# circuitPendulum8TIA.net
KiCad netlist of a schematic drawn in EAGLE
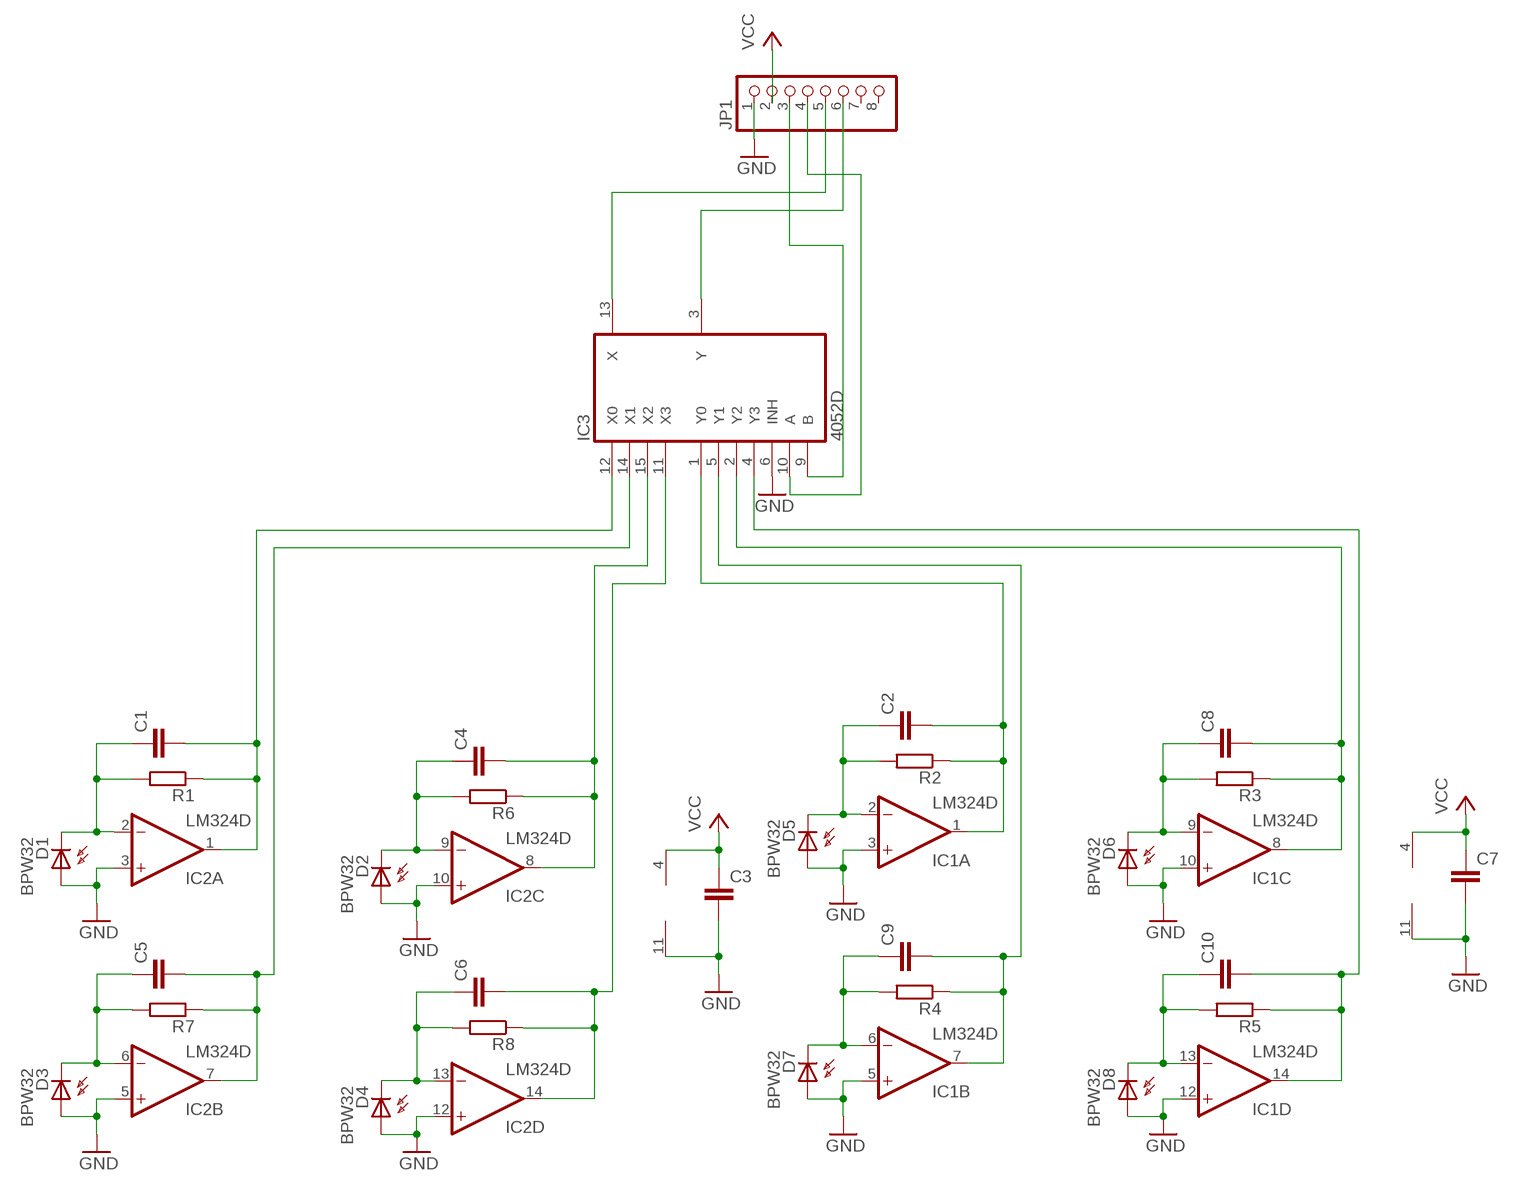
[diagram p0: schematic, sheet 1]

(export (version "E")
  (design (tool "Eeschema 10.0.6"))
  (components
    (comp (ref "C1")
      (value "C-EUC0603")
      (footprint "eagle-import:C0603")
      (libsource (lib "eagle-import") (part "C-EUC0603"))
    )
    (comp (ref "C2")
      (value "C-EUC0603")
      (footprint "eagle-import:C0603")
      (libsource (lib "eagle-import") (part "C-EUC0603"))
    )
    (comp (ref "C3")
      (value "C-EUC0603")
      (footprint "eagle-import:C0603")
      (libsource (lib "eagle-import") (part "C-EUC0603"))
    )
    (comp (ref "C4")
      (value "C-EUC0603")
      (footprint "eagle-import:C0603")
      (libsource (lib "eagle-import") (part "C-EUC0603"))
    )
    (comp (ref "C5")
      (value "C-EUC0603")
      (footprint "eagle-import:C0603")
      (libsource (lib "eagle-import") (part "C-EUC0603"))
    )
    (comp (ref "C6")
      (value "C-EUC0603")
      (footprint "eagle-import:C0603")
      (libsource (lib "eagle-import") (part "C-EUC0603"))
    )
    (comp (ref "C7")
      (value "C-EUC0603")
      (footprint "eagle-import:C0603")
      (libsource (lib "eagle-import") (part "C-EUC0603"))
    )
    (comp (ref "C8")
      (value "C-EUC0603")
      (footprint "eagle-import:C0603")
      (libsource (lib "eagle-import") (part "C-EUC0603"))
    )
    (comp (ref "C9")
      (value "C-EUC0603")
      (footprint "eagle-import:C0603")
      (libsource (lib "eagle-import") (part "C-EUC0603"))
    )
    (comp (ref "C10")
      (value "C-EUC0603")
      (footprint "eagle-import:C0603")
      (libsource (lib "eagle-import") (part "C-EUC0603"))
    )
    (comp (ref "D1")
      (value "BPW32")
      (footprint "eagle-import:BPW32")
      (libsource (lib "eagle-import") (part "BPW32"))
    )
    (comp (ref "D2")
      (value "BPW32")
      (footprint "eagle-import:BPW32")
      (libsource (lib "eagle-import") (part "BPW32"))
    )
    (comp (ref "D3")
      (value "BPW32")
      (footprint "eagle-import:BPW32")
      (libsource (lib "eagle-import") (part "BPW32"))
    )
    (comp (ref "D4")
      (value "BPW32")
      (footprint "eagle-import:BPW32")
      (libsource (lib "eagle-import") (part "BPW32"))
    )
    (comp (ref "D5")
      (value "BPW32")
      (footprint "eagle-import:BPW32")
      (libsource (lib "eagle-import") (part "BPW32"))
    )
    (comp (ref "D6")
      (value "BPW32")
      (footprint "eagle-import:BPW32")
      (libsource (lib "eagle-import") (part "BPW32"))
    )
    (comp (ref "D7")
      (value "BPW32")
      (footprint "eagle-import:BPW32")
      (libsource (lib "eagle-import") (part "BPW32"))
    )
    (comp (ref "D8")
      (value "BPW32")
      (footprint "eagle-import:BPW32")
      (libsource (lib "eagle-import") (part "BPW32"))
    )
    (comp (ref "IC1")
      (value "LM324D")
      (footprint "eagle-import:SO14")
      (libsource (lib "eagle-import") (part "LM324D"))
    )
    (comp (ref "IC2")
      (value "LM324D")
      (footprint "eagle-import:SO14")
      (libsource (lib "eagle-import") (part "LM324D"))
    )
    (comp (ref "IC3")
      (value "4052D")
      (footprint "eagle-import:SO16")
      (libsource (lib "eagle-import") (part "4052D"))
    )
    (comp (ref "JP1")
      (value "PINHD-1X8_2.54")
      (footprint "eagle-import:1X08")
      (libsource (lib "eagle-import") (part "PINHD-1X8_2.54"))
    )
    (comp (ref "R1")
      (value "R-EU_R0603")
      (footprint "eagle-import:R0603")
      (libsource (lib "eagle-import") (part "R-EU_R0603"))
    )
    (comp (ref "R2")
      (value "R-EU_R0603")
      (footprint "eagle-import:R0603")
      (libsource (lib "eagle-import") (part "R-EU_R0603"))
    )
    (comp (ref "R3")
      (value "R-EU_R0603")
      (footprint "eagle-import:R0603")
      (libsource (lib "eagle-import") (part "R-EU_R0603"))
    )
    (comp (ref "R4")
      (value "R-EU_R0603")
      (footprint "eagle-import:R0603")
      (libsource (lib "eagle-import") (part "R-EU_R0603"))
    )
    (comp (ref "R5")
      (value "R-EU_R0603")
      (footprint "eagle-import:R0603")
      (libsource (lib "eagle-import") (part "R-EU_R0603"))
    )
    (comp (ref "R6")
      (value "R-EU_R0603")
      (footprint "eagle-import:R0603")
      (libsource (lib "eagle-import") (part "R-EU_R0603"))
    )
    (comp (ref "R7")
      (value "R-EU_R0603")
      (footprint "eagle-import:R0603")
      (libsource (lib "eagle-import") (part "R-EU_R0603"))
    )
    (comp (ref "R8")
      (value "R-EU_R0603")
      (footprint "eagle-import:R0603")
      (libsource (lib "eagle-import") (part "R-EU_R0603"))
    )
  )
  (nets
    (net (code "1") (name "GND") (class "Default")
      (node (ref "C3") (pin "2") (pinfunction "2_2") (pintype "passive"))
      (node (ref "C7") (pin "2") (pinfunction "2_2") (pintype "passive"))
      (node (ref "D1") (pin "A") (pinfunction "A_A") (pintype "passive"))
      (node (ref "D2") (pin "A") (pinfunction "A_A") (pintype "passive"))
      (node (ref "D3") (pin "A") (pinfunction "A_A") (pintype "passive"))
      (node (ref "D4") (pin "A") (pinfunction "A_A") (pintype "passive"))
      (node (ref "D5") (pin "A") (pinfunction "A_A") (pintype "passive"))
      (node (ref "D6") (pin "A") (pinfunction "A_A") (pintype "passive"))
      (node (ref "D7") (pin "A") (pinfunction "A_A") (pintype "passive"))
      (node (ref "D8") (pin "A") (pinfunction "A_A") (pintype "passive"))
      (node (ref "IC1") (pin "10") (pinfunction "+IN_10") (pintype "input"))
      (node (ref "IC1") (pin "11") (pinfunction "V-_11") (pintype "power_in"))
      (node (ref "IC1") (pin "12") (pinfunction "+IN_12") (pintype "input"))
      (node (ref "IC1") (pin "3") (pinfunction "+IN_3") (pintype "input"))
      (node (ref "IC1") (pin "5") (pinfunction "+IN_5") (pintype "input"))
      (node (ref "IC2") (pin "10") (pinfunction "+IN_10") (pintype "input"))
      (node (ref "IC2") (pin "11") (pinfunction "V-_11") (pintype "power_in"))
      (node (ref "IC2") (pin "12") (pinfunction "+IN_12") (pintype "input"))
      (node (ref "IC2") (pin "3") (pinfunction "+IN_3") (pintype "input"))
      (node (ref "IC2") (pin "5") (pinfunction "+IN_5") (pintype "input"))
      (node (ref "IC3") (pin "6") (pinfunction "INH_6") (pintype "input"))
      (node (ref "JP1") (pin "1") (pinfunction "1_1") (pintype "passive"))
    )
    (net (code "2") (name "Net-(D1-C)") (class "Default")
      (node (ref "C1") (pin "1") (pinfunction "1_1") (pintype "passive"))
      (node (ref "D1") (pin "K") (pinfunction "C_K") (pintype "passive"))
      (node (ref "IC2") (pin "2") (pinfunction "-IN_2") (pintype "input"))
      (node (ref "R1") (pin "2") (pinfunction "2_2") (pintype "passive"))
    )
    (net (code "3") (name "Net-(D2-C)") (class "Default")
      (node (ref "C4") (pin "1") (pinfunction "1_1") (pintype "passive"))
      (node (ref "D2") (pin "K") (pinfunction "C_K") (pintype "passive"))
      (node (ref "IC2") (pin "9") (pinfunction "-IN_9") (pintype "input"))
      (node (ref "R6") (pin "2") (pinfunction "2_2") (pintype "passive"))
    )
    (net (code "4") (name "Net-(D3-C)") (class "Default")
      (node (ref "C5") (pin "1") (pinfunction "1_1") (pintype "passive"))
      (node (ref "D3") (pin "K") (pinfunction "C_K") (pintype "passive"))
      (node (ref "IC2") (pin "6") (pinfunction "-IN_6") (pintype "input"))
      (node (ref "R7") (pin "2") (pinfunction "2_2") (pintype "passive"))
    )
    (net (code "5") (name "Net-(D4-C)") (class "Default")
      (node (ref "C6") (pin "1") (pinfunction "1_1") (pintype "passive"))
      (node (ref "D4") (pin "K") (pinfunction "C_K") (pintype "passive"))
      (node (ref "IC2") (pin "13") (pinfunction "-IN_13") (pintype "input"))
      (node (ref "R8") (pin "2") (pinfunction "2_2") (pintype "passive"))
    )
    (net (code "6") (name "Net-(D5-C)") (class "Default")
      (node (ref "C2") (pin "1") (pinfunction "1_1") (pintype "passive"))
      (node (ref "D5") (pin "K") (pinfunction "C_K") (pintype "passive"))
      (node (ref "IC1") (pin "2") (pinfunction "-IN_2") (pintype "input"))
      (node (ref "R2") (pin "2") (pinfunction "2_2") (pintype "passive"))
    )
    (net (code "7") (name "Net-(D6-C)") (class "Default")
      (node (ref "C8") (pin "1") (pinfunction "1_1") (pintype "passive"))
      (node (ref "D6") (pin "K") (pinfunction "C_K") (pintype "passive"))
      (node (ref "IC1") (pin "9") (pinfunction "-IN_9") (pintype "input"))
      (node (ref "R3") (pin "2") (pinfunction "2_2") (pintype "passive"))
    )
    (net (code "8") (name "Net-(D7-C)") (class "Default")
      (node (ref "C9") (pin "1") (pinfunction "1_1") (pintype "passive"))
      (node (ref "D7") (pin "K") (pinfunction "C_K") (pintype "passive"))
      (node (ref "IC1") (pin "6") (pinfunction "-IN_6") (pintype "input"))
      (node (ref "R4") (pin "2") (pinfunction "2_2") (pintype "passive"))
    )
    (net (code "9") (name "Net-(D8-C)") (class "Default")
      (node (ref "C10") (pin "1") (pinfunction "1_1") (pintype "passive"))
      (node (ref "D8") (pin "K") (pinfunction "C_K") (pintype "passive"))
      (node (ref "IC1") (pin "13") (pinfunction "-IN_13") (pintype "input"))
      (node (ref "R5") (pin "2") (pinfunction "2_2") (pintype "passive"))
    )
    (net (code "10") (name "Net-(IC1A-OUT)") (class "Default")
      (node (ref "C2") (pin "2") (pinfunction "2_2") (pintype "passive"))
      (node (ref "IC1") (pin "1") (pinfunction "OUT_1") (pintype "output"))
      (node (ref "IC3") (pin "1") (pinfunction "Y0_1") (pintype "bidirectional"))
      (node (ref "R2") (pin "1") (pinfunction "1_1") (pintype "passive"))
    )
    (net (code "11") (name "Net-(IC1B-OUT)") (class "Default")
      (node (ref "C9") (pin "2") (pinfunction "2_2") (pintype "passive"))
      (node (ref "IC1") (pin "7") (pinfunction "OUT_7") (pintype "output"))
      (node (ref "IC3") (pin "5") (pinfunction "Y1_5") (pintype "bidirectional"))
      (node (ref "R4") (pin "1") (pinfunction "1_1") (pintype "passive"))
    )
    (net (code "12") (name "Net-(IC1C-OUT)") (class "Default")
      (node (ref "C8") (pin "2") (pinfunction "2_2") (pintype "passive"))
      (node (ref "IC1") (pin "8") (pinfunction "OUT_8") (pintype "output"))
      (node (ref "IC3") (pin "2") (pinfunction "Y2_2") (pintype "bidirectional"))
      (node (ref "R3") (pin "1") (pinfunction "1_1") (pintype "passive"))
    )
    (net (code "13") (name "Net-(IC1D-OUT)") (class "Default")
      (node (ref "C10") (pin "2") (pinfunction "2_2") (pintype "passive"))
      (node (ref "IC1") (pin "14") (pinfunction "OUT_14") (pintype "output"))
      (node (ref "IC3") (pin "4") (pinfunction "Y3_4") (pintype "bidirectional"))
      (node (ref "R5") (pin "1") (pinfunction "1_1") (pintype "passive"))
    )
    (net (code "14") (name "Net-(IC2A-OUT)") (class "Default")
      (node (ref "C1") (pin "2") (pinfunction "2_2") (pintype "passive"))
      (node (ref "IC2") (pin "1") (pinfunction "OUT_1") (pintype "output"))
      (node (ref "IC3") (pin "12") (pinfunction "X0_12") (pintype "bidirectional"))
      (node (ref "R1") (pin "1") (pinfunction "1_1") (pintype "passive"))
    )
    (net (code "15") (name "Net-(IC2B-OUT)") (class "Default")
      (node (ref "C5") (pin "2") (pinfunction "2_2") (pintype "passive"))
      (node (ref "IC2") (pin "7") (pinfunction "OUT_7") (pintype "output"))
      (node (ref "IC3") (pin "14") (pinfunction "X1_14") (pintype "bidirectional"))
      (node (ref "R7") (pin "1") (pinfunction "1_1") (pintype "passive"))
    )
    (net (code "16") (name "Net-(IC2C-OUT)") (class "Default")
      (node (ref "C4") (pin "2") (pinfunction "2_2") (pintype "passive"))
      (node (ref "IC2") (pin "8") (pinfunction "OUT_8") (pintype "output"))
      (node (ref "IC3") (pin "15") (pinfunction "X2_15") (pintype "bidirectional"))
      (node (ref "R6") (pin "1") (pinfunction "1_1") (pintype "passive"))
    )
    (net (code "17") (name "Net-(IC2D-OUT)") (class "Default")
      (node (ref "C6") (pin "2") (pinfunction "2_2") (pintype "passive"))
      (node (ref "IC2") (pin "14") (pinfunction "OUT_14") (pintype "output"))
      (node (ref "IC3") (pin "11") (pinfunction "X3_11") (pintype "bidirectional"))
      (node (ref "R8") (pin "1") (pinfunction "1_1") (pintype "passive"))
    )
    (net (code "18") (name "Net-(IC3A-A)") (class "Default")
      (node (ref "IC3") (pin "10") (pinfunction "A_10") (pintype "input"))
      (node (ref "JP1") (pin "4") (pinfunction "4_4") (pintype "passive"))
    )
    (net (code "19") (name "Net-(IC3A-B)") (class "Default")
      (node (ref "IC3") (pin "9") (pinfunction "B_9") (pintype "input"))
      (node (ref "JP1") (pin "3") (pinfunction "3_3") (pintype "passive"))
    )
    (net (code "20") (name "Net-(IC3A-X)") (class "Default")
      (node (ref "IC3") (pin "13") (pinfunction "X_13") (pintype "bidirectional"))
      (node (ref "JP1") (pin "5") (pinfunction "5_5") (pintype "passive"))
    )
    (net (code "21") (name "Net-(IC3A-Y)") (class "Default")
      (node (ref "IC3") (pin "3") (pinfunction "Y_3") (pintype "bidirectional"))
      (node (ref "JP1") (pin "6") (pinfunction "6_6") (pintype "passive"))
    )
    (net (code "22") (name "VCC") (class "Default")
      (node (ref "C3") (pin "1") (pinfunction "1_1") (pintype "passive"))
      (node (ref "C7") (pin "1") (pinfunction "1_1") (pintype "passive"))
      (node (ref "IC1") (pin "4") (pinfunction "V+_4") (pintype "power_in"))
      (node (ref "IC2") (pin "4") (pinfunction "V+_4") (pintype "power_in"))
      (node (ref "JP1") (pin "2") (pinfunction "2_2") (pintype "passive"))
    )
    (net (code "23") (name "unconnected-(JP1-Pad7)") (class "Default")
      (node (ref "JP1") (pin "7") (pinfunction "7_7") (pintype "passive"))
    )
    (net (code "24") (name "unconnected-(JP1-Pad8)") (class "Default")
      (node (ref "JP1") (pin "8") (pinfunction "8_8") (pintype "passive"))
    )
  )
)
